# jn5169_v1.net
KiCad netlist of a schematic drawn in EAGLE
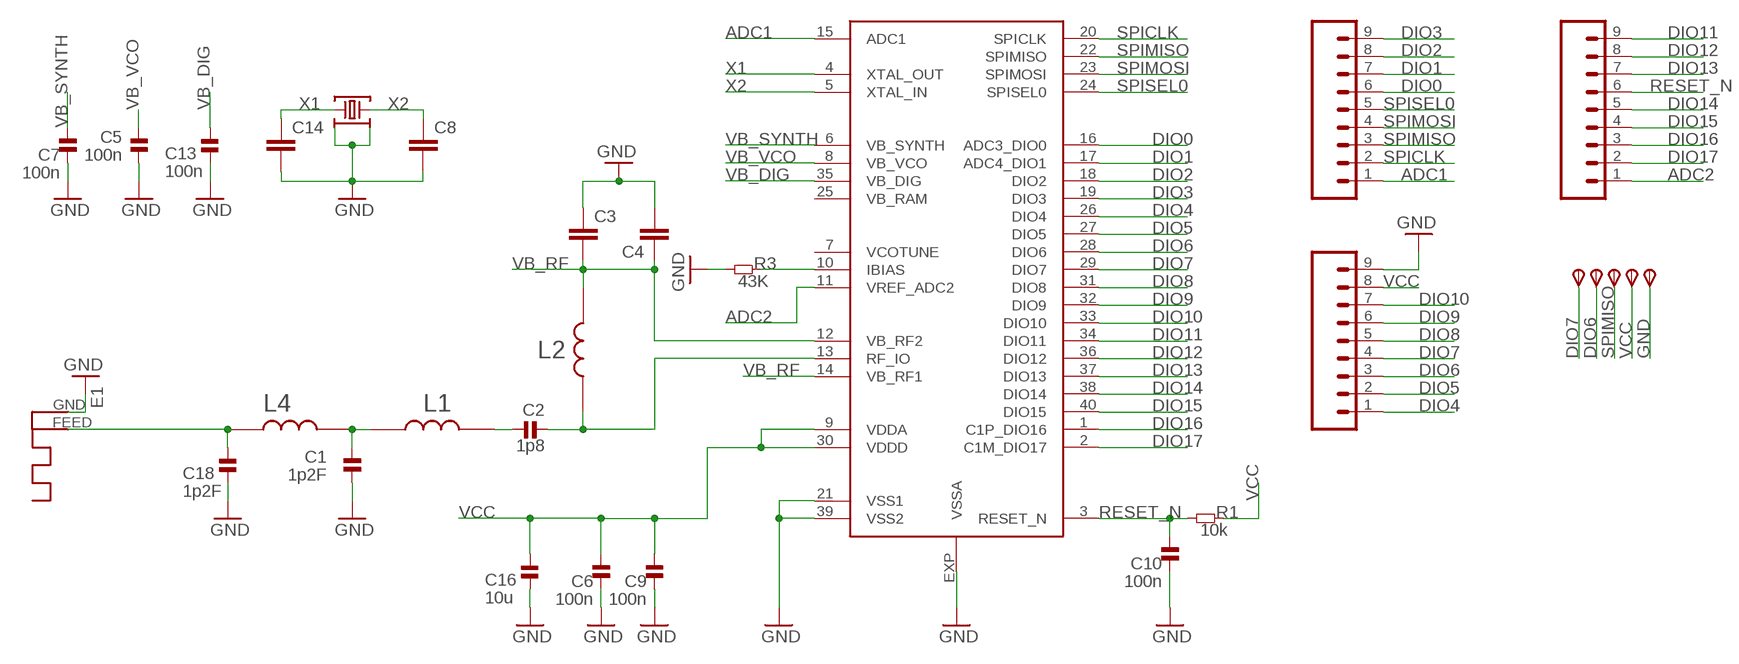
[diagram p0: schematic, sheet 1]

(export (version "E")
  (design (tool "Eeschema 10.0.6"))
  (components
    (comp (ref "C1")
      (value "1p2F")
      (footprint "eagle-import:_PKG_C_0402")
      (libsource (lib "eagle-import") (part "CAP-0402"))
    )
    (comp (ref "C2")
      (value "1p8")
      (footprint "eagle-import:_PKG_C_0402")
      (libsource (lib "eagle-import") (part "CAP-0402"))
    )
    (comp (ref "C3")
      (value "100n")
      (footprint "eagle-import:CAPC1005X40N")
      (fields (field (name "MF") "Yageo") (field (name "MP") "RC0402FR-073M6L"))
      (libsource (lib "eagle-import") (part "CAP0402"))
    )
    (comp (ref "C4")
      (value "47pf")
      (footprint "eagle-import:CAPC1005X40N")
      (fields (field (name "MF") "Yageo") (field (name "MP") "RC0402FR-073M6L"))
      (libsource (lib "eagle-import") (part "CAP0402"))
    )
    (comp (ref "C5")
      (value "100n")
      (footprint "eagle-import:_PKG_C_0402")
      (libsource (lib "eagle-import") (part "CAP-0402"))
    )
    (comp (ref "C6")
      (value "100n")
      (footprint "eagle-import:_PKG_C_0402")
      (libsource (lib "eagle-import") (part "CAP-0402"))
    )
    (comp (ref "C7")
      (value "100n")
      (footprint "eagle-import:_PKG_C_0402")
      (libsource (lib "eagle-import") (part "CAP-0402"))
    )
    (comp (ref "C8")
      (value "12p")
      (footprint "eagle-import:CAPC1005X40N")
      (fields (field (name "MF") "Yageo") (field (name "MP") "RC0402FR-073M6L"))
      (libsource (lib "eagle-import") (part "CAP0402"))
    )
    (comp (ref "C9")
      (value "100n")
      (footprint "eagle-import:_PKG_C_0402")
      (libsource (lib "eagle-import") (part "CAP-0402"))
    )
    (comp (ref "C10")
      (value "100n")
      (footprint "eagle-import:_PKG_C_0402")
      (libsource (lib "eagle-import") (part "CAP-0402"))
    )
    (comp (ref "C13")
      (value "100n")
      (footprint "eagle-import:_PKG_C_0402")
      (libsource (lib "eagle-import") (part "CAP-0402"))
    )
    (comp (ref "C14")
      (value "12p")
      (footprint "eagle-import:CAPC1005X40N")
      (fields (field (name "MF") "Yageo") (field (name "MP") "RC0402FR-073M6L"))
      (libsource (lib "eagle-import") (part "CAP0402"))
    )
    (comp (ref "C16")
      (value "10u")
      (footprint "eagle-import:_PKG_C_0805")
      (libsource (lib "eagle-import") (part "CAP-0805"))
    )
    (comp (ref "C18")
      (value "1p2F")
      (footprint "eagle-import:_PKG_C_0402")
      (libsource (lib "eagle-import") (part "CAP-0402"))
    )
    (comp (ref "E1")
      (value "ANTENNA")
      (footprint "eagle-import:RN-ANT")
      (libsource (lib "eagle-import") (part "ANTENNA"))
    )
    (comp (ref "GND")
      (value "TPSTP11R")
      (footprint "eagle-import:TP11R")
      (libsource (lib "eagle-import") (part "TPSTP11R"))
    )
    (comp (ref "J1")
      (value "CONN_051.27MM")
      (footprint "eagle-import:1X05_1.27MM")
      (libsource (lib "eagle-import") (part "CONN_051.27MM"))
    )
    (comp (ref "J2")
      (value "CONN_051.27MM")
      (footprint "eagle-import:1X05_1.27MM")
      (libsource (lib "eagle-import") (part "CONN_051.27MM"))
    )
    (comp (ref "J3")
      (value "CONN_051.27MM")
      (footprint "eagle-import:1X05_1.27MM")
      (libsource (lib "eagle-import") (part "CONN_051.27MM"))
    )
    (comp (ref "L1")
      (value "3n3H")
      (footprint "eagle-import:INDC1005X40N")
      (fields (field (name "MF") "Yageo") (field (name "MP") "RC0402FR-073M6L"))
      (libsource (lib "eagle-import") (part "IND0402IND0402"))
    )
    (comp (ref "L2")
      (value "1n5H")
      (footprint "eagle-import:INDC1005X40N")
      (fields (field (name "MF") "Yageo") (field (name "MP") "RC0402FR-073M6L"))
      (libsource (lib "eagle-import") (part "IND0402IND0402"))
    )
    (comp (ref "L4")
      (value "2n7H")
      (footprint "eagle-import:INDC1005X40N")
      (fields (field (name "MF") "Yageo") (field (name "MP") "RC0402FR-073M6L"))
      (libsource (lib "eagle-import") (part "IND0402IND0402"))
    )
    (comp (ref "R1")
      (value "10k")
      (footprint "eagle-import:_PKG_C_0402")
      (libsource (lib "eagle-import") (part "RES-0402"))
    )
    (comp (ref "R3")
      (value "43K")
      (footprint "eagle-import:_PKG_C_0402")
      (libsource (lib "eagle-import") (part "RES-0402"))
    )
    (comp (ref "RX")
      (value "TPSTP11R")
      (footprint "eagle-import:TP11R")
      (libsource (lib "eagle-import") (part "TPSTP11R"))
    )
    (comp (ref "TDO")
      (value "TPSTP11R")
      (footprint "eagle-import:TP11R")
      (libsource (lib "eagle-import") (part "TPSTP11R"))
    )
    (comp (ref "TX")
      (value "TPSTP11R")
      (footprint "eagle-import:TP11R")
      (libsource (lib "eagle-import") (part "TPSTP11R"))
    )
    (comp (ref "U$1")
      (value "JN5168/A02Z")
      (footprint "eagle-import:QFN50P600X600X100-41N")
      (fields (field (name "MF") "NXP Semiconductors"))
      (libsource (lib "eagle-import") (part "JN5168/A02Z"))
    )
    (comp (ref "VCC")
      (value "TPSTP11R")
      (footprint "eagle-import:TP11R")
      (libsource (lib "eagle-import") (part "TPSTP11R"))
    )
    (comp (ref "Y1")
      (value "32MHZ")
      (footprint "eagle-import:XTAL-4P-2016")
      (fields (field (name "DIGIKEY_PART") "1253-2042-1-ND") (field (name "MFG_PART") "CX2016DB48000C0FPLC1"))
      (libsource (lib "eagle-import") (part "48.000MHZ_CX2016DB48000C0FPLC1"))
    )
  )
  (nets
    (net (code "1") (name "/ADC1") (class "Default")
      (node (ref "J1") (pin "1") (pinfunction "1_1") (pintype "passive"))
      (node (ref "U$1") (pin "15") (pinfunction "ADC1_15") (pintype "power_in"))
    )
    (net (code "2") (name "/ADC2") (class "Default")
      (node (ref "J3") (pin "1") (pinfunction "1_1") (pintype "passive"))
      (node (ref "U$1") (pin "11") (pinfunction "VREF_ADC2_11") (pintype "power_in"))
    )
    (net (code "3") (name "/DIO0") (class "Default")
      (node (ref "J1") (pin "6") (pinfunction "6_6") (pintype "passive"))
      (node (ref "U$1") (pin "16") (pinfunction "ADC3_DIO0_16") (pintype "bidirectional"))
    )
    (net (code "4") (name "/DIO1") (class "Default")
      (node (ref "J1") (pin "7") (pinfunction "7_7") (pintype "passive"))
      (node (ref "U$1") (pin "17") (pinfunction "ADC4_DIO1_17") (pintype "bidirectional"))
    )
    (net (code "5") (name "/DIO2") (class "Default")
      (node (ref "J1") (pin "8") (pinfunction "8_8") (pintype "passive"))
      (node (ref "U$1") (pin "18") (pinfunction "DIO2_18") (pintype "bidirectional"))
    )
    (net (code "6") (name "/DIO3") (class "Default")
      (node (ref "J1") (pin "9") (pinfunction "9_9") (pintype "passive"))
      (node (ref "U$1") (pin "19") (pinfunction "DIO3_19") (pintype "bidirectional"))
    )
    (net (code "7") (name "/DIO4") (class "Default")
      (node (ref "J2") (pin "1") (pinfunction "1_1") (pintype "passive"))
      (node (ref "U$1") (pin "26") (pinfunction "DIO4_26") (pintype "bidirectional"))
    )
    (net (code "8") (name "/DIO5") (class "Default")
      (node (ref "J2") (pin "2") (pinfunction "2_2") (pintype "passive"))
      (node (ref "U$1") (pin "27") (pinfunction "DIO5_27") (pintype "bidirectional"))
    )
    (net (code "9") (name "/DIO6") (class "Default")
      (node (ref "J2") (pin "3") (pinfunction "3_3") (pintype "passive"))
      (node (ref "TX") (pin "TP") (pinfunction "PP_TP") (pintype "input"))
      (node (ref "U$1") (pin "28") (pinfunction "DIO6_28") (pintype "bidirectional"))
    )
    (net (code "10") (name "/DIO7") (class "Default")
      (node (ref "J2") (pin "4") (pinfunction "4_4") (pintype "passive"))
      (node (ref "RX") (pin "TP") (pinfunction "PP_TP") (pintype "input"))
      (node (ref "U$1") (pin "29") (pinfunction "DIO7_29") (pintype "bidirectional"))
    )
    (net (code "11") (name "/DIO8") (class "Default")
      (node (ref "J2") (pin "5") (pinfunction "5_5") (pintype "passive"))
      (node (ref "U$1") (pin "31") (pinfunction "DIO8_31") (pintype "bidirectional"))
    )
    (net (code "12") (name "/DIO9") (class "Default")
      (node (ref "J2") (pin "6") (pinfunction "6_6") (pintype "passive"))
      (node (ref "U$1") (pin "32") (pinfunction "DIO9_32") (pintype "bidirectional"))
    )
    (net (code "13") (name "/DIO10") (class "Default")
      (node (ref "J2") (pin "7") (pinfunction "7_7") (pintype "passive"))
      (node (ref "U$1") (pin "33") (pinfunction "DIO10_33") (pintype "bidirectional"))
    )
    (net (code "14") (name "/DIO11") (class "Default")
      (node (ref "J3") (pin "9") (pinfunction "9_9") (pintype "passive"))
      (node (ref "U$1") (pin "34") (pinfunction "DIO11_34") (pintype "bidirectional"))
    )
    (net (code "15") (name "/DIO12") (class "Default")
      (node (ref "J3") (pin "8") (pinfunction "8_8") (pintype "passive"))
      (node (ref "U$1") (pin "36") (pinfunction "DIO12_36") (pintype "bidirectional"))
    )
    (net (code "16") (name "/DIO13") (class "Default")
      (node (ref "J3") (pin "7") (pinfunction "7_7") (pintype "passive"))
      (node (ref "U$1") (pin "37") (pinfunction "DIO13_37") (pintype "bidirectional"))
    )
    (net (code "17") (name "/DIO14") (class "Default")
      (node (ref "J3") (pin "5") (pinfunction "5_5") (pintype "passive"))
      (node (ref "U$1") (pin "38") (pinfunction "DIO14_38") (pintype "bidirectional"))
    )
    (net (code "18") (name "/DIO15") (class "Default")
      (node (ref "J3") (pin "4") (pinfunction "4_4") (pintype "passive"))
      (node (ref "U$1") (pin "40") (pinfunction "DIO15_40") (pintype "bidirectional"))
    )
    (net (code "19") (name "/DIO16") (class "Default")
      (node (ref "J3") (pin "3") (pinfunction "3_3") (pintype "passive"))
      (node (ref "U$1") (pin "1") (pinfunction "C1P_DIO16_1") (pintype "bidirectional"))
    )
    (net (code "20") (name "/DIO17") (class "Default")
      (node (ref "J3") (pin "2") (pinfunction "2_2") (pintype "passive"))
      (node (ref "U$1") (pin "2") (pinfunction "C1M_DIO17_2") (pintype "bidirectional"))
    )
    (net (code "21") (name "/RESET_N") (class "Default")
      (node (ref "C10") (pin "2") (pinfunction "2_2") (pintype "passive"))
      (node (ref "J3") (pin "6") (pinfunction "6_6") (pintype "passive"))
      (node (ref "R1") (pin "2") (pinfunction "2_2") (pintype "passive"))
      (node (ref "U$1") (pin "3") (pinfunction "RESET_N_3") (pintype "input"))
    )
    (net (code "22") (name "/SPICLK") (class "Default")
      (node (ref "J1") (pin "2") (pinfunction "2_2") (pintype "passive"))
      (node (ref "U$1") (pin "20") (pinfunction "SPICLK_20") (pintype "output"))
    )
    (net (code "23") (name "/SPIMISO") (class "Default")
      (node (ref "J1") (pin "3") (pinfunction "3_3") (pintype "passive"))
      (node (ref "TDO") (pin "TP") (pinfunction "PP_TP") (pintype "input"))
      (node (ref "U$1") (pin "22") (pinfunction "SPIMISO_22") (pintype "output"))
    )
    (net (code "24") (name "/SPIMOSI") (class "Default")
      (node (ref "J1") (pin "4") (pinfunction "4_4") (pintype "passive"))
      (node (ref "U$1") (pin "23") (pinfunction "SPIMOSI_23") (pintype "bidirectional"))
    )
    (net (code "25") (name "/SPISEL0") (class "Default")
      (node (ref "J1") (pin "5") (pinfunction "5_5") (pintype "passive"))
      (node (ref "U$1") (pin "24") (pinfunction "SPISEL0_24") (pintype "bidirectional"))
    )
    (net (code "26") (name "/VB_DIG") (class "Default")
      (node (ref "C13") (pin "1") (pinfunction "1_1") (pintype "passive"))
      (node (ref "U$1") (pin "35") (pinfunction "VB_DIG_35") (pintype "power_in"))
    )
    (net (code "27") (name "/VB_RAM") (class "Default")
      (node (ref "U$1") (pin "25") (pinfunction "VB_RAM_25") (pintype "power_in"))
    )
    (net (code "28") (name "/VB_RF") (class "Default")
      (node (ref "C3") (pin "2") (pinfunction "2_2") (pintype "passive"))
      (node (ref "C4") (pin "1") (pinfunction "1_1") (pintype "passive"))
      (node (ref "L2") (pin "2") (pinfunction "2_2") (pintype "passive"))
      (node (ref "U$1") (pin "12") (pinfunction "VB_RF2_12") (pintype "power_in"))
      (node (ref "U$1") (pin "14") (pinfunction "VB_RF1_14") (pintype "power_in"))
    )
    (net (code "29") (name "/VB_SYNTH") (class "Default")
      (node (ref "C7") (pin "2") (pinfunction "2_2") (pintype "passive"))
      (node (ref "U$1") (pin "6") (pinfunction "VB_SYNTH_6") (pintype "power_in"))
    )
    (net (code "30") (name "/VB_VCO") (class "Default")
      (node (ref "C5") (pin "2") (pinfunction "2_2") (pintype "passive"))
      (node (ref "U$1") (pin "8") (pinfunction "VB_VCO_8") (pintype "power_in"))
    )
    (net (code "31") (name "/VCC") (class "Default")
      (node (ref "C16") (pin "1") (pinfunction "1_1") (pintype "passive"))
      (node (ref "C6") (pin "2") (pinfunction "2_2") (pintype "passive"))
      (node (ref "C9") (pin "2") (pinfunction "2_2") (pintype "passive"))
      (node (ref "J2") (pin "8") (pinfunction "8_8") (pintype "passive"))
      (node (ref "R1") (pin "1") (pinfunction "1_1") (pintype "passive"))
      (node (ref "U$1") (pin "30") (pinfunction "VDDD_30") (pintype "power_in"))
      (node (ref "U$1") (pin "9") (pinfunction "VDDA_9") (pintype "power_in"))
      (node (ref "VCC") (pin "TP") (pinfunction "PP_TP") (pintype "input"))
    )
    (net (code "32") (name "/VCOTUNE") (class "Default")
      (node (ref "U$1") (pin "7") (pinfunction "VCOTUNE_7") (pintype "power_in"))
    )
    (net (code "33") (name "/X1") (class "Default")
      (node (ref "C14") (pin "1") (pinfunction "1_1") (pintype "passive"))
      (node (ref "U$1") (pin "4") (pinfunction "XTAL_OUT_4") (pintype "output"))
      (node (ref "Y1") (pin "1") (pinfunction "1_1") (pintype "passive"))
    )
    (net (code "34") (name "/X2") (class "Default")
      (node (ref "C8") (pin "1") (pinfunction "1_1") (pintype "passive"))
      (node (ref "U$1") (pin "5") (pinfunction "XTAL_IN_5") (pintype "input"))
      (node (ref "Y1") (pin "3") (pinfunction "3_3") (pintype "passive"))
    )
    (net (code "35") (name "GND") (class "Default")
      (node (ref "C1") (pin "1") (pinfunction "1_1") (pintype "passive"))
      (node (ref "C10") (pin "1") (pinfunction "1_1") (pintype "passive"))
      (node (ref "C13") (pin "2") (pinfunction "2_2") (pintype "passive"))
      (node (ref "C14") (pin "2") (pinfunction "2_2") (pintype "passive"))
      (node (ref "C16") (pin "2") (pinfunction "2_2") (pintype "passive"))
      (node (ref "C18") (pin "2") (pinfunction "2_2") (pintype "passive"))
      (node (ref "C3") (pin "1") (pinfunction "1_1") (pintype "passive"))
      (node (ref "C4") (pin "2") (pinfunction "2_2") (pintype "passive"))
      (node (ref "C5") (pin "1") (pinfunction "1_1") (pintype "passive"))
      (node (ref "C6") (pin "1") (pinfunction "1_1") (pintype "passive"))
      (node (ref "C7") (pin "1") (pinfunction "1_1") (pintype "passive"))
      (node (ref "C8") (pin "2") (pinfunction "2_2") (pintype "passive"))
      (node (ref "C9") (pin "1") (pinfunction "1_1") (pintype "passive"))
      (node (ref "E1") (pin "GND") (pinfunction "GND_GND") (pintype "passive"))
      (node (ref "GND") (pin "TP") (pinfunction "PP_TP") (pintype "input"))
      (node (ref "J2") (pin "9") (pinfunction "9_9") (pintype "passive"))
      (node (ref "R3") (pin "2") (pinfunction "2_2") (pintype "passive"))
      (node (ref "U$1") (pin "21") (pinfunction "VSS1_21") (pintype "power_in"))
      (node (ref "U$1") (pin "39") (pinfunction "VSS2_39") (pintype "power_in"))
      (node (ref "U$1") (pin "EXP") (pinfunction "VSSA_EXP") (pintype "power_in"))
      (node (ref "Y1") (pin "2") (pinfunction "2_2") (pintype "bidirectional"))
      (node (ref "Y1") (pin "4") (pinfunction "4_4") (pintype "bidirectional"))
    )
    (net (code "36") (name "Net-(C1-Pad2)") (class "Default")
      (node (ref "C1") (pin "2") (pinfunction "2_2") (pintype "passive"))
      (node (ref "L1") (pin "1") (pinfunction "1_1") (pintype "passive"))
      (node (ref "L4") (pin "2") (pinfunction "2_2") (pintype "passive"))
    )
    (net (code "37") (name "Net-(C2-Pad2)") (class "Default")
      (node (ref "C2") (pin "2") (pinfunction "2_2") (pintype "passive"))
      (node (ref "L1") (pin "2") (pinfunction "2_2") (pintype "passive"))
    )
    (net (code "38") (name "Net-(C18-Pad1)") (class "Default")
      (node (ref "C18") (pin "1") (pinfunction "1_1") (pintype "passive"))
      (node (ref "E1") (pin "FEED") (pinfunction "FEED_FEED") (pintype "passive"))
      (node (ref "L4") (pin "1") (pinfunction "1_1") (pintype "passive"))
    )
    (net (code "39") (name "Net-(U$1-IBIAS)") (class "Default")
      (node (ref "R3") (pin "1") (pinfunction "1_1") (pintype "passive"))
      (node (ref "U$1") (pin "10") (pinfunction "IBIAS_10") (pintype "input"))
    )
    (net (code "40") (name "Net-(U$1-RF_IO)") (class "Default")
      (node (ref "C2") (pin "1") (pinfunction "1_1") (pintype "passive"))
      (node (ref "L2") (pin "1") (pinfunction "1_1") (pintype "passive"))
      (node (ref "U$1") (pin "13") (pinfunction "RF_IO_13") (pintype "input"))
    )
  )
)
